# CABLE_TEST.net
KiCad netlist of a schematic drawn in Altium Designer
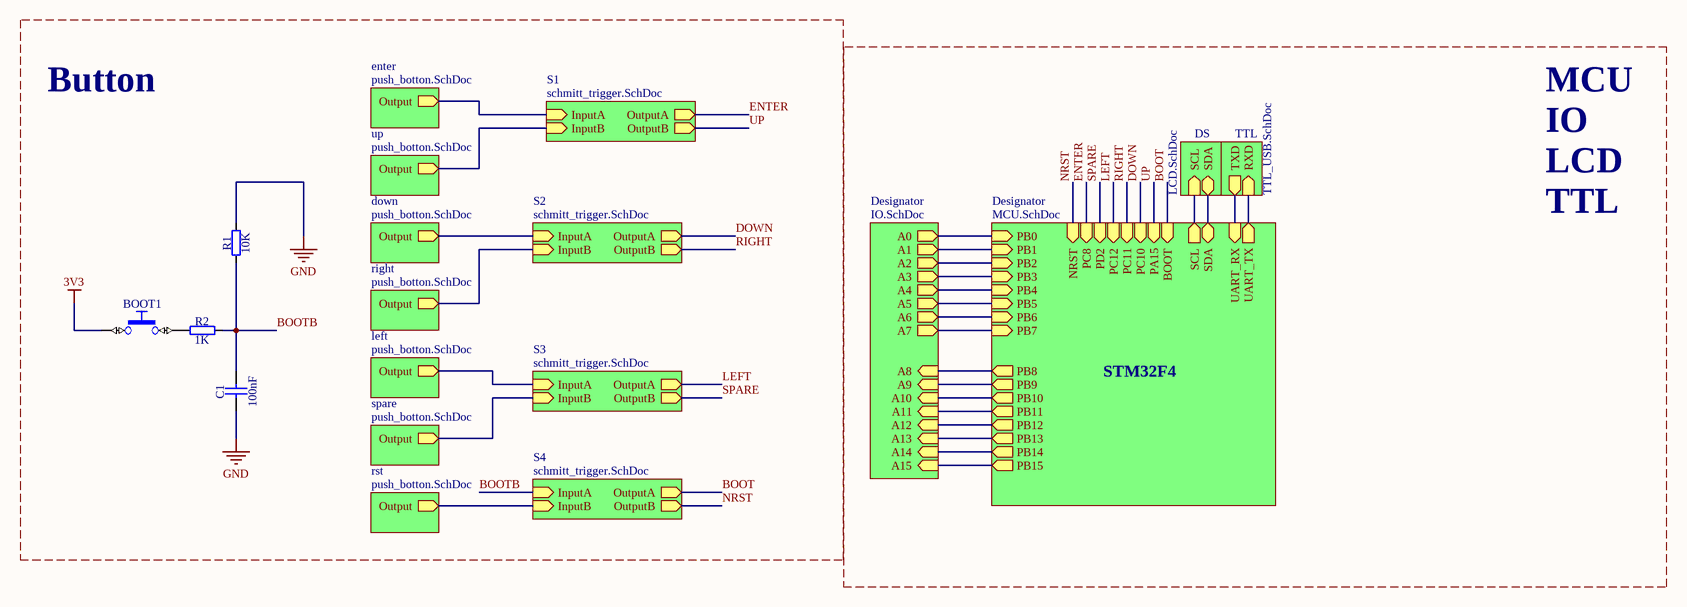
[diagram p0: CABLE_TEST.SchDoc]

(export (version "E")
  (design (tool "Eeschema 10.0.6"))
  (components
    (comp (ref "BOOT1")
      (value "Push Button")
      (footprint "PB_TYCO_FSMSM")
      (description "Push-Button Switch SPST")
      (fields
        (field (name "PART NUMBER") "PB_TYCO_FSMSM")
        (field (name "MANUFACTURER") "TYCO ELECTRONICS")
        (field (name "AUTHOR") "CERN DEM JLC")
      )
      (libsource (lib "Eletro-mechanical") (part "PB SPST 1NO-2NO"))
    )
    (comp (ref "C1")
      (value "100nF")
      (footprint "CAPC2012X135N")
      (description "Non-polarised capacitor")
      (fields
        (field (name "PART NUMBER") "CC0805_100NF_50V_10%_X7R")
        (field (name "VOLTAGE") "50V")
        (field (name "AUTHOR") "CERN DEM JLC")
      )
      (libsource (lib "Capacitors") (part "Capacitor - non polarized"))
    )
    (comp (ref "R1")
      (value "10K")
      (footprint "RESC2012X60N")
      (description "Resistor - 1%")
      (fields
        (field (name "PART NUMBER") "R0805_24K_1%_0.125W_100PPM")
        (field (name "POWER") "0.125W")
        (field (name "AUTHOR") "CERN DEM JLC")
      )
      (libsource (lib "Resistors") (part "Resistor - 1%"))
    )
    (comp (ref "R2")
      (value "1K")
      (footprint "RESC2012X60N")
      (description "Resistor - 1%")
      (fields
        (field (name "PART NUMBER") "R0805_24K_1%_0.125W_100PPM")
        (field (name "POWER") "0.125W")
        (field (name "AUTHOR") "CERN DEM JLC")
      )
      (libsource (lib "Resistors") (part "Resistor - 1%"))
    )
  )
  (nets
    (net (code "10") (name "/BOOTB") (class "Default")
      (node (ref "C1") (pin "2") (pinfunction "2_2") (pintype "passive"))
      (node (ref "R1") (pin "1") (pinfunction "1_1") (pintype "passive"))
      (node (ref "R2") (pin "2") (pinfunction "2_2") (pintype "passive"))
    )
    (net (code "37") (name "3V3") (class "Default")
      (node (ref "BOOT1") (pin "1") (pinfunction "1_1") (pintype "bidirectional"))
    )
    (net (code "38") (name "GND") (class "Default")
      (node (ref "C1") (pin "1") (pinfunction "1_1") (pintype "passive"))
      (node (ref "R1") (pin "2") (pinfunction "2_2") (pintype "passive"))
    )
    (net (code "39") (name "Net-(BOOT1-Pad2)") (class "Default")
      (node (ref "BOOT1") (pin "2") (pinfunction "2_2") (pintype "bidirectional"))
      (node (ref "R2") (pin "1") (pinfunction "1_1") (pintype "passive"))
    )
  )
)
